# headstage-64-coax-adapter_rev1_2.net
KiCad netlist of a schematic drawn in EAGLE
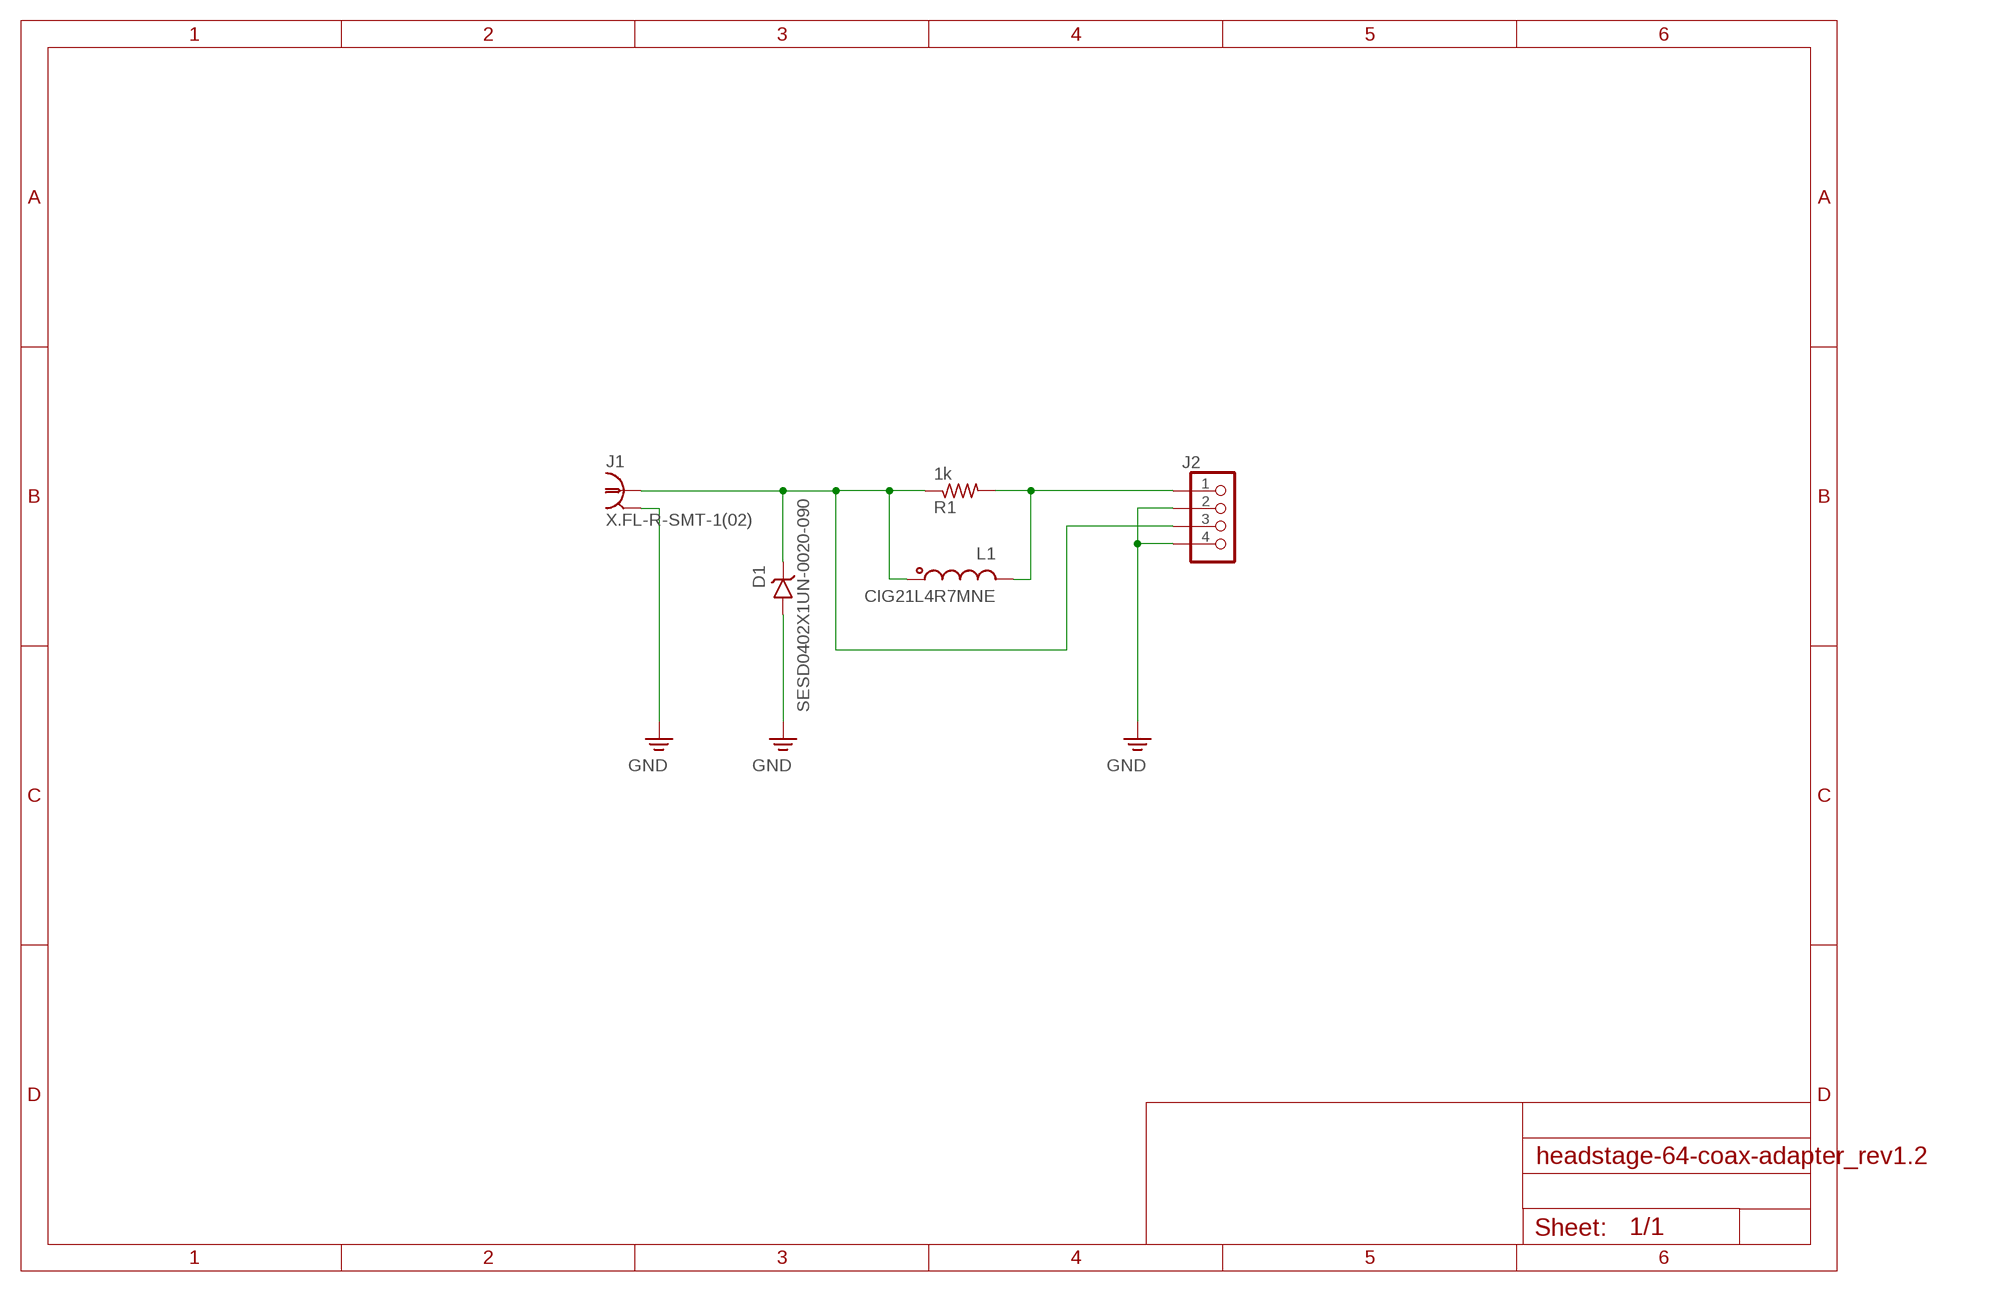
[diagram p0: schematic, sheet 1]

(export (version "E")
  (design (tool "Eeschema 10.0.6"))
  (components
    (comp (ref "D1")
      (value "SESD0402X1UN-0020-090")
      (footprint "eagle-import:0402T-DFN")
      (libsource (lib "eagle-import") (part "Z-DIODE_0402T-DFN"))
    )
    (comp (ref "J1")
      (value "X.FL-R-SMT-1(02)")
      (footprint "eagle-import:X_FL_R_SMT_1(02)")
      (libsource (lib "eagle-import") (part "COAX_XFL"))
    )
    (comp (ref "J2")
      (value "PINHD-1X4HEADSTAGE64-DAUGHTER-CARD-CASTELLATED")
      (footprint "eagle-import:HEADSTAGE64-DAUGHER-CARD-CASTELLATED")
      (libsource (lib "eagle-import") (part "PINHD-1X4HEADSTAGE64-DAUGHTER-CARD-CASTELLATED"))
    )
    (comp (ref "L1")
      (value "CIG21L4R7MNE")
      (footprint "eagle-import:0805T")
      (libsource (lib "eagle-import") (part "L_0805T"))
    )
    (comp (ref "R1")
      (value "1k")
      (footprint "eagle-import:0201T")
      (libsource (lib "eagle-import") (part "R_0201T"))
    )
  )
  (nets
    (net (code "1") (name "GND") (class "Default")
      (node (ref "D1") (pin "A") (pinfunction "A_A") (pintype "passive"))
      (node (ref "J1") (pin "P$2") (pinfunction "2_P$2") (pintype "passive"))
      (node (ref "J1") (pin "P$3") (pinfunction "2_P$3") (pintype "passive"))
      (node (ref "J1") (pin "P$4") (pinfunction "2_P$4") (pintype "passive"))
      (node (ref "J2") (pin "2") (pinfunction "2_2") (pintype "passive"))
      (node (ref "J2") (pin "4") (pinfunction "4_4") (pintype "passive"))
    )
    (net (code "2") (name "Net-(J1-1)") (class "Default")
      (node (ref "D1") (pin "C") (pinfunction "C_C") (pintype "passive"))
      (node (ref "J1") (pin "P$1") (pinfunction "1_P$1") (pintype "passive"))
      (node (ref "J2") (pin "3") (pinfunction "3_3") (pintype "passive"))
      (node (ref "L1") (pin "1") (pinfunction "1_1") (pintype "passive"))
      (node (ref "R1") (pin "1") (pinfunction "1_1") (pintype "passive"))
    )
    (net (code "3") (name "Net-(J2-Pad1)") (class "Default")
      (node (ref "J2") (pin "1") (pinfunction "1_1") (pintype "passive"))
      (node (ref "L1") (pin "2") (pinfunction "2_2") (pintype "passive"))
      (node (ref "R1") (pin "2") (pinfunction "2_2") (pintype "passive"))
    )
  )
)
